# FastCharge.net
KiCad netlist of a schematic drawn in Altium Designer
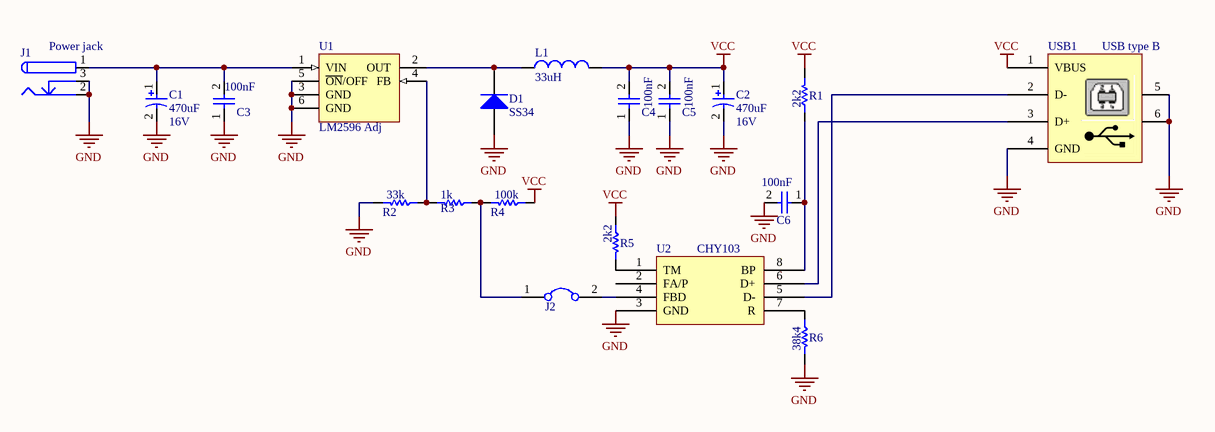
[diagram p0: FastCharge.SchDoc]

(export (version "E")
  (design (tool "Eeschema 10.0.6"))
  (components
    (comp (ref "C1")
      (value "470uF")
      (footprint "Cap 3.5mm")
      (fields (field (name "ALTIUM_UNNAMED_8") "16V"))
      (libsource (lib "3D LIB") (part "CAP"))
    )
    (comp (ref "C2")
      (value "470uF")
      (footprint "Cap 3.5mm")
      (fields (field (name "ALTIUM_UNNAMED_8") "16V"))
      (libsource (lib "3D LIB") (part "CAP"))
    )
    (comp (ref "C3") (value "100nF") (footprint "SMD 0805") (libsource (lib "3D LIB") (part "CAP NON")))
    (comp (ref "C4") (value "100nF") (footprint "SMD 0805") (libsource (lib "3D LIB") (part "CAP NON")))
    (comp (ref "C5") (value "100nF") (footprint "SMD 0805") (libsource (lib "3D LIB") (part "CAP NON")))
    (comp (ref "C6") (value "100nF") (footprint "SMD 0805") (libsource (lib "3D LIB") (part "CAP NON")))
    (comp (ref "D1")
      (value "SS34")
      (footprint "DIODE DO-214AC SMD")
      (libsource (lib "3D LIB") (part "Diode"))
    )
    (comp (ref "J1")
      (value "Power jack")
      (footprint "Power Jack")
      (fields (field (name "ALTIUM_UNNAMED_1") "Power jack"))
      (libsource (lib "3D LIB") (part "Power jack"))
    )
    (comp (ref "J2")
      (value "JUMPER")
      (footprint "Jumper Header 2X1")
      (libsource (lib "3D LIB") (part "JUMPER"))
    )
    (comp (ref "L1")
      (value "33uH")
      (footprint "Inductor 5.8mm")
      (description "Inductor")
      (libsource (lib "3D LIB") (part "Inductor"))
    )
    (comp (ref "R1") (value "2k2") (footprint "0805_1/8W") (libsource (lib "3D LIB") (part "RESISTOR")))
    (comp (ref "R2") (value "33k") (footprint "0805_1/8W") (libsource (lib "3D LIB") (part "RESISTOR")))
    (comp (ref "R3") (value "1k") (footprint "0805_1/8W") (libsource (lib "3D LIB") (part "RESISTOR")))
    (comp (ref "R4") (value "100k") (footprint "0805_1/8W") (libsource (lib "3D LIB") (part "RESISTOR")))
    (comp (ref "R5") (value "2k2") (footprint "0805_1/8W") (libsource (lib "3D LIB") (part "RESISTOR")))
    (comp (ref "R6") (value "38k4") (footprint "0805_1/8W") (libsource (lib "3D LIB") (part "RESISTOR")))
    (comp (ref "U1")
      (value "LM2596 Adj")
      (footprint "TO-263 5 LEAD")
      (libsource (lib "3D LIB") (part "LM2576 SMD"))
    )
    (comp (ref "U2")
      (value "CHY103")
      (footprint "SOIC 8-Lead  (3.8mm)")
      (libsource (lib "Schlib") (part "CHY103"))
    )
    (comp (ref "USB1")
      (value "USB Connector-B Type")
      (footprint "USB2.5-2H4C")
      (fields (field (name "ALTIUM_UNNAMED_2") "USB type B"))
      (libsource (lib "3D LIB") (part "USB Connector-B Type"))
    )
  )
  (nets
    (net (code "1") (name "GND") (class "Default")
      (node (ref "C1") (pin "2") (pinfunction "2_2") (pintype "passive"))
      (node (ref "C2") (pin "2") (pinfunction "2_2") (pintype "passive"))
      (node (ref "C3") (pin "1") (pinfunction "1_1") (pintype "passive"))
      (node (ref "C4") (pin "1") (pinfunction "1_1") (pintype "passive"))
      (node (ref "C5") (pin "1") (pinfunction "1_1") (pintype "passive"))
      (node (ref "C6") (pin "2") (pinfunction "2_2") (pintype "passive"))
      (node (ref "D1") (pin "1") (pinfunction "A_1") (pintype "passive"))
      (node (ref "J1") (pin "2") (pinfunction "2_2") (pintype "power_in"))
      (node (ref "J1") (pin "3") (pinfunction "3_3") (pintype "power_in"))
      (node (ref "R2") (pin "2") (pinfunction "2_2") (pintype "passive"))
      (node (ref "R6") (pin "2") (pinfunction "2_2") (pintype "passive"))
      (node (ref "U1") (pin "3") (pinfunction "GND_3") (pintype "power_in"))
      (node (ref "U1") (pin "5") (pinfunction "~{ON}/OFF_5") (pintype "passive"))
      (node (ref "U1") (pin "6") (pinfunction "GND_6") (pintype "power_in"))
      (node (ref "U2") (pin "3") (pinfunction "GND_3") (pintype "passive"))
      (node (ref "USB1") (pin "4") (pinfunction "GND_4") (pintype "power_in"))
      (node (ref "USB1") (pin "5") (pinfunction "5_5") (pintype "passive"))
      (node (ref "USB1") (pin "6") (pinfunction "6_6") (pintype "passive"))
    )
    (net (code "2") (name "Net-(D1-K)") (class "Default")
      (node (ref "D1") (pin "2") (pinfunction "K_2") (pintype "passive"))
      (node (ref "L1") (pin "1") (pinfunction "1_1") (pintype "passive"))
      (node (ref "U1") (pin "2") (pinfunction "OUT_2") (pintype "open_emitter"))
    )
    (net (code "3") (name "Net-(J2-Pad1)") (class "Default")
      (node (ref "J2") (pin "1") (pinfunction "1_1") (pintype "passive"))
      (node (ref "R3") (pin "1") (pinfunction "1_1") (pintype "passive"))
      (node (ref "R4") (pin "2") (pinfunction "2_2") (pintype "passive"))
    )
    (net (code "4") (name "Net-(U1-FB)") (class "Default")
      (node (ref "R2") (pin "1") (pinfunction "1_1") (pintype "passive"))
      (node (ref "R3") (pin "2") (pinfunction "2_2") (pintype "passive"))
      (node (ref "U1") (pin "4") (pinfunction "FB_4") (pintype "input"))
    )
    (net (code "5") (name "Net-(U1-VIN)") (class "Default")
      (node (ref "C1") (pin "1") (pinfunction "1_1") (pintype "passive"))
      (node (ref "C3") (pin "2") (pinfunction "2_2") (pintype "passive"))
      (node (ref "J1") (pin "1") (pinfunction "1_1") (pintype "power_in"))
      (node (ref "U1") (pin "1") (pinfunction "VIN_1") (pintype "input"))
    )
    (net (code "6") (name "Net-(U2-BP)") (class "Default")
      (node (ref "C6") (pin "1") (pinfunction "1_1") (pintype "passive"))
      (node (ref "R1") (pin "1") (pinfunction "1_1") (pintype "passive"))
      (node (ref "U2") (pin "8") (pinfunction "BP_8") (pintype "passive"))
    )
    (net (code "7") (name "Net-(U2-D+)") (class "Default")
      (node (ref "U2") (pin "6") (pinfunction "D+_6") (pintype "passive"))
      (node (ref "USB1") (pin "3") (pinfunction "D+_3") (pintype "passive"))
    )
    (net (code "8") (name "Net-(U2-D-)") (class "Default")
      (node (ref "U2") (pin "5") (pinfunction "D-_5") (pintype "passive"))
      (node (ref "USB1") (pin "2") (pinfunction "D-_2") (pintype "passive"))
    )
    (net (code "9") (name "Net-(U2-FBD)") (class "Default")
      (node (ref "J2") (pin "2") (pinfunction "2_2") (pintype "passive"))
      (node (ref "U2") (pin "4") (pinfunction "FBD_4") (pintype "passive"))
    )
    (net (code "10") (name "Net-(U2-R)") (class "Default")
      (node (ref "R6") (pin "1") (pinfunction "1_1") (pintype "passive"))
      (node (ref "U2") (pin "7") (pinfunction "R_7") (pintype "passive"))
    )
    (net (code "11") (name "Net-(U2-TM)") (class "Default")
      (node (ref "R5") (pin "2") (pinfunction "2_2") (pintype "passive"))
      (node (ref "U2") (pin "1") (pinfunction "TM_1") (pintype "passive"))
    )
    (net (code "12") (name "VCC") (class "Default")
      (node (ref "C2") (pin "1") (pinfunction "1_1") (pintype "passive"))
      (node (ref "C4") (pin "2") (pinfunction "2_2") (pintype "passive"))
      (node (ref "C5") (pin "2") (pinfunction "2_2") (pintype "passive"))
      (node (ref "L1") (pin "2") (pinfunction "2_2") (pintype "passive"))
      (node (ref "R1") (pin "2") (pinfunction "2_2") (pintype "passive"))
      (node (ref "R4") (pin "1") (pinfunction "1_1") (pintype "passive"))
      (node (ref "R5") (pin "1") (pinfunction "1_1") (pintype "passive"))
      (node (ref "USB1") (pin "1") (pinfunction "VBUS_1") (pintype "power_in"))
    )
    (net (code "13") (name "unconnected-(U2-FA{slash}P-Pad2)") (class "Default")
      (node (ref "U2") (pin "2") (pinfunction "FA/P_2") (pintype "passive"))
    )
  )
)
